# EasyEDA_SmartMeter-Reader.net
KiCad netlist of a schematic drawn in EasyEDA
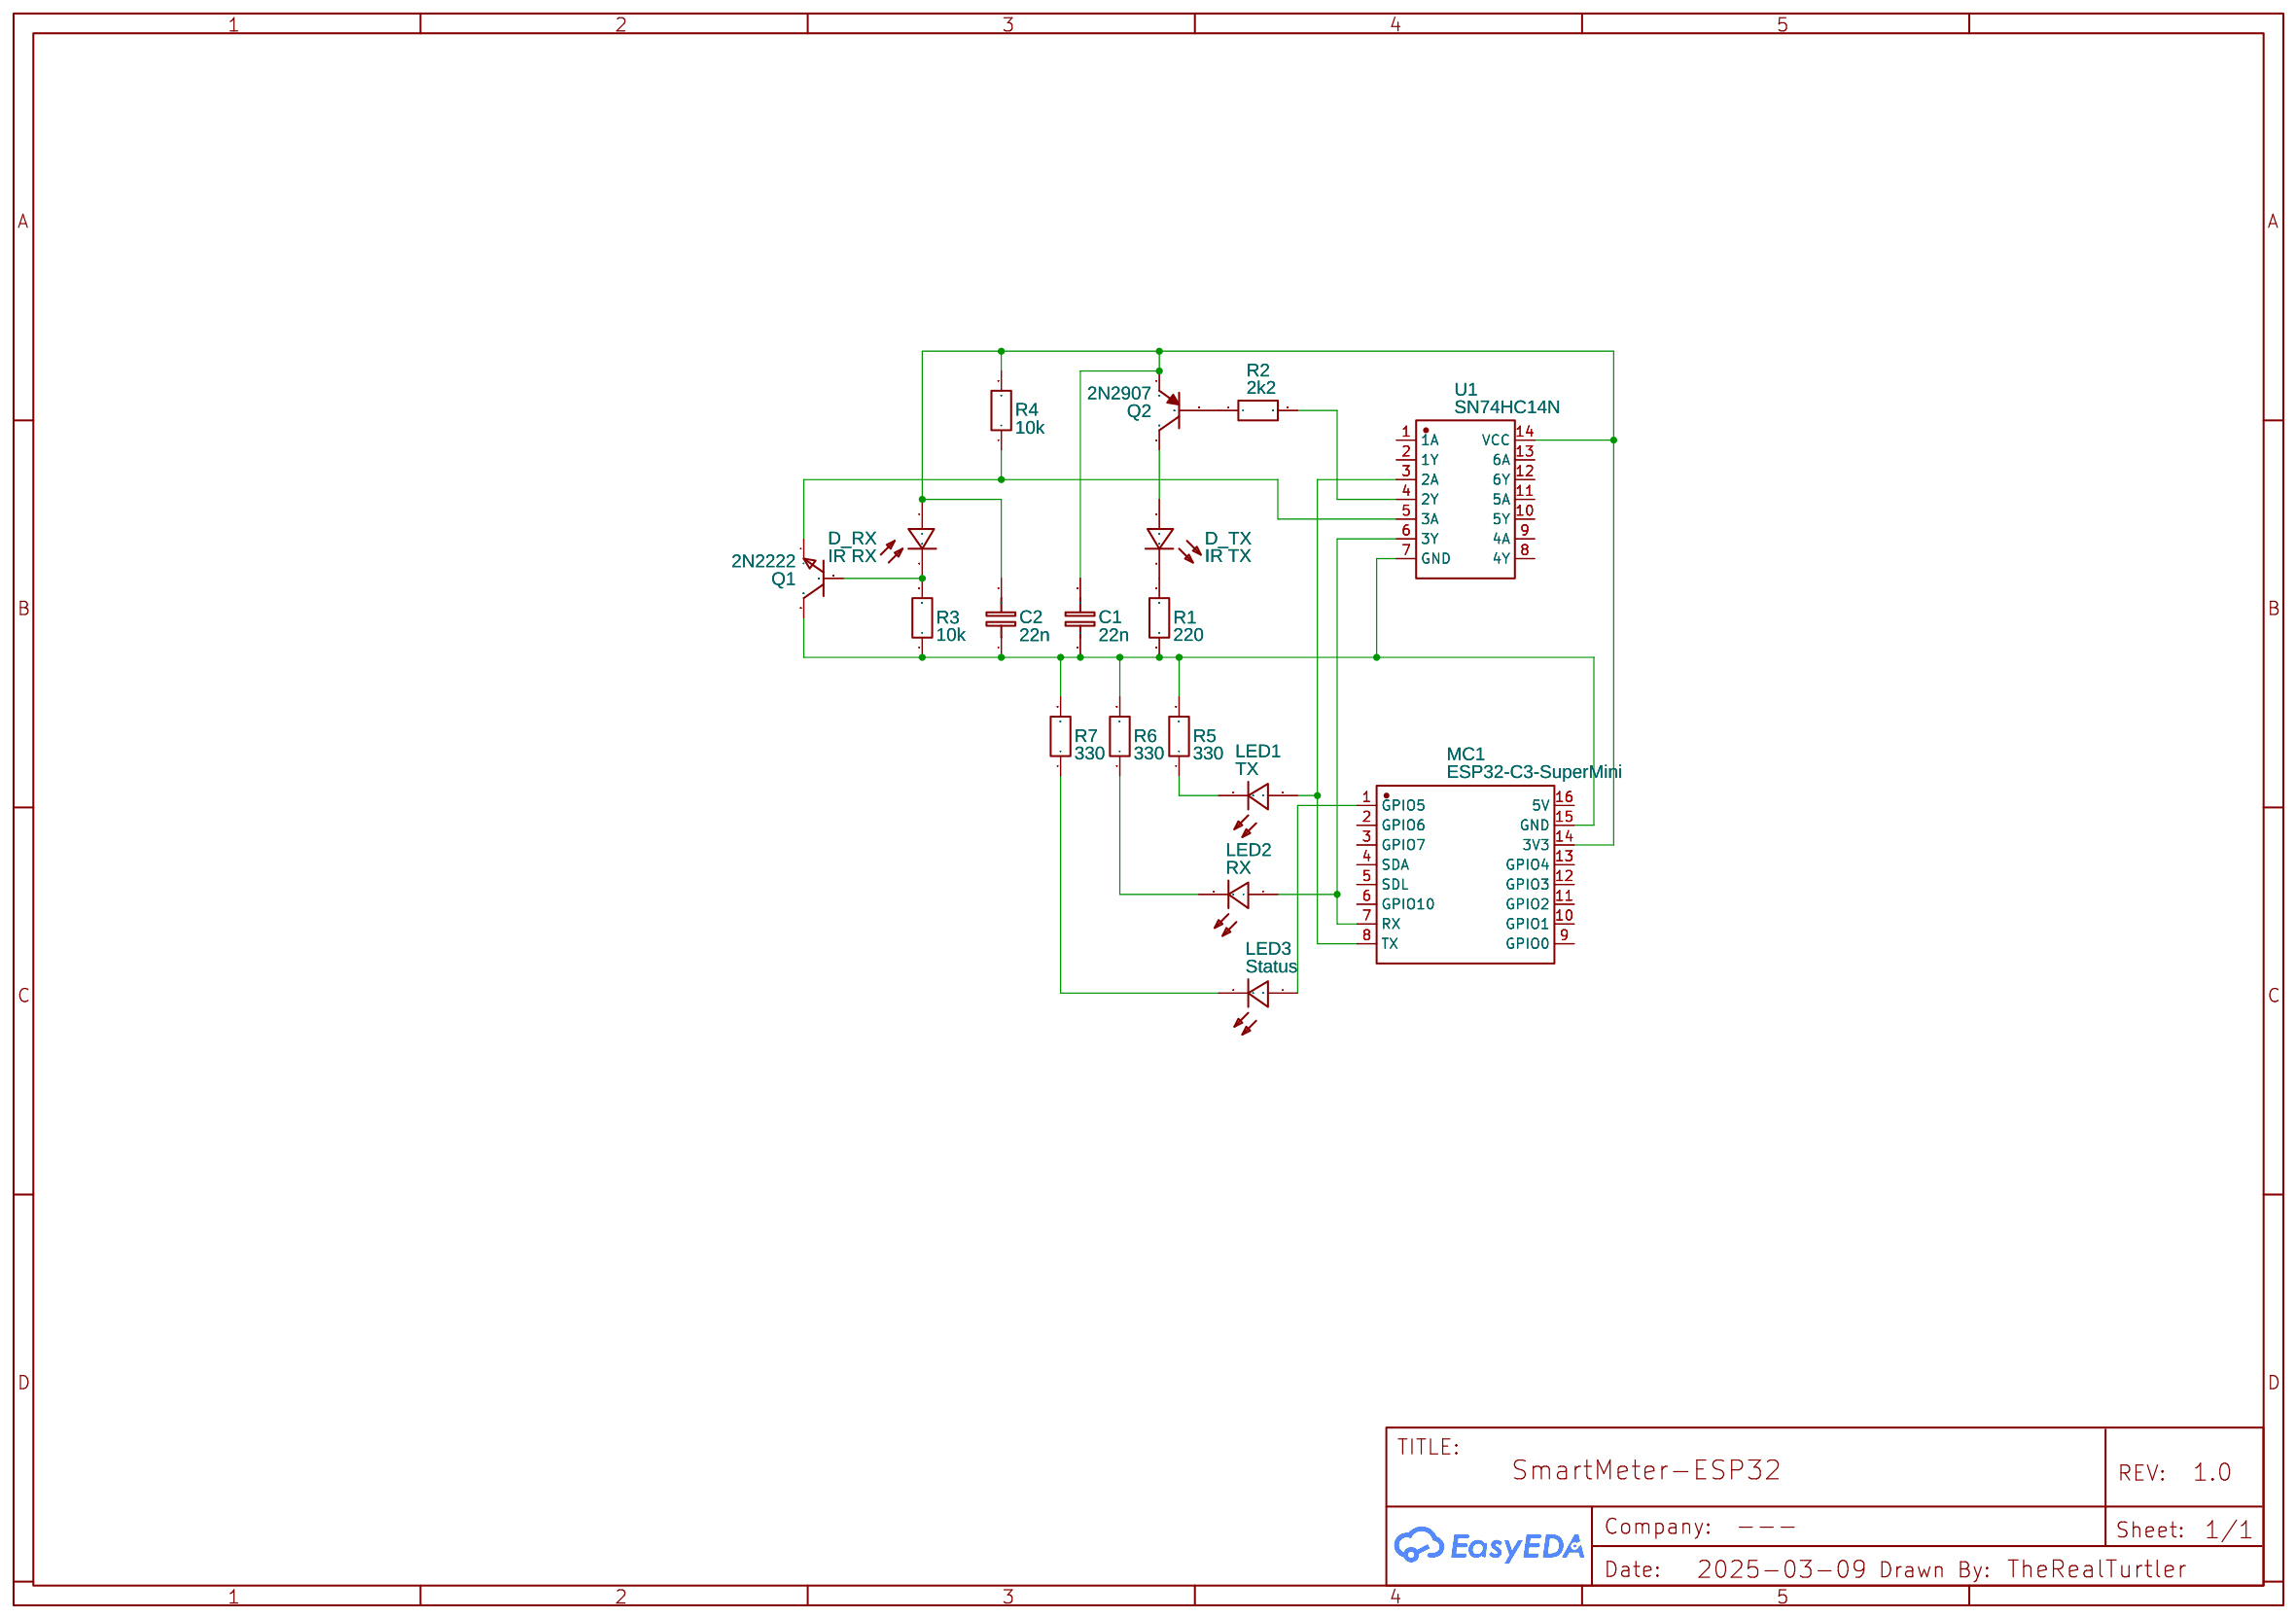
[diagram p0: schematic sheet]

(export (version "E")
  (design (tool "Eeschema 10.0.6"))
  (components
    (comp (ref "C1") (value "22n") (libsource (lib "") (part "C_0603_EU_1")))
    (comp (ref "C2") (value "22n") (libsource (lib "") (part "C_0603_EU")))
    (comp (ref "D_RX") (value "IR RX") (libsource (lib "") (part "Photodiode 3mm")))
    (comp (ref "D_TX")
      (value "IR TX")
      (fields (field (name "Manufacturer Part") "LED-TH-3mm_R"))
      (libsource (lib "") (part "LED-TH-3MM_R"))
    )
    (comp (ref "LED1")
      (value "TX")
      (fields (field (name "Manufacturer Part") "LED-TH-3mm_R"))
      (libsource (lib "") (part "LED-TH-3MM_R_1"))
    )
    (comp (ref "LED2")
      (value "RX")
      (fields (field (name "Manufacturer Part") "LED-TH-3mm_R"))
      (libsource (lib "") (part "LED-TH-3MM_R_1"))
    )
    (comp (ref "LED3")
      (value "Status")
      (fields (field (name "Manufacturer Part") "LED-TH-3mm_R"))
      (libsource (lib "") (part "LED-TH-3MM_R_1"))
    )
    (comp (ref "MC1") (value "ESP32-C3-SuperMini") (libsource (lib "") (part "ESP32-C3-SuperMini")))
    (comp (ref "Q1")
      (value "2N2222")
      (fields (field (name "Manufacturer Part") "2N2222A") (field (name "Manufacturer") "ST(先科)"))
      (libsource (lib "") (part "2N2222"))
    )
    (comp (ref "Q2")
      (value "2N2907")
      (fields (field (name "Manufacturer Part") "2N2907A") (field (name "Manufacturer") "ST(先科)"))
      (libsource (lib "") (part "2N2907"))
    )
    (comp (ref "R1") (value "220") (libsource (lib "") (part "R_0603_EU")))
    (comp (ref "R2") (value "2k2") (libsource (lib "") (part "R_0603_EU_1")))
    (comp (ref "R3") (value "10k") (libsource (lib "") (part "R_0603_EU")))
    (comp (ref "R4") (value "10k") (libsource (lib "") (part "R_0603_EU")))
    (comp (ref "R5") (value "330") (libsource (lib "") (part "R_0603_EU")))
    (comp (ref "R6") (value "330") (libsource (lib "") (part "R_0603_EU")))
    (comp (ref "R7") (value "330") (libsource (lib "") (part "R_0603_EU")))
    (comp (ref "U1")
      (value "SN74HC14N")
      (fields (field (name "Manufacturer") "TI(德州仪器)"))
      (libsource (lib "") (part "SN74HC14N"))
    )
  )
  (nets
    (net (code "1") (name "Net-(D_TX-Pad2)") (class "Default")
      (node (ref "D_TX") (pin "2") (pinfunction "2_2") (pintype "unspecified"))
      (node (ref "R1") (pin "2") (pinfunction "2_2") (pintype "unspecified"))
    )
    (net (code "2") (name "Net-(LED1-Pad2)") (class "Default")
      (node (ref "LED1") (pin "2") (pinfunction "2_2") (pintype "unspecified"))
      (node (ref "R5") (pin "1") (pinfunction "1_1") (pintype "unspecified"))
    )
    (net (code "3") (name "Net-(LED2-Pad2)") (class "Default")
      (node (ref "LED2") (pin "2") (pinfunction "2_2") (pintype "unspecified"))
      (node (ref "R6") (pin "1") (pinfunction "1_1") (pintype "unspecified"))
    )
    (net (code "4") (name "Net-(LED3-Pad2)") (class "Default")
      (node (ref "LED3") (pin "2") (pinfunction "2_2") (pintype "unspecified"))
      (node (ref "R7") (pin "1") (pinfunction "1_1") (pintype "unspecified"))
    )
    (net (code "5") (name "Net-(MC1-3V3)") (class "Default")
      (node (ref "C1") (pin "2") (pinfunction "2_2") (pintype "unspecified"))
      (node (ref "C2") (pin "2") (pinfunction "2_2") (pintype "unspecified"))
      (node (ref "D_RX") (pin "1") (pinfunction "1_1") (pintype "unspecified"))
      (node (ref "MC1") (pin "14") (pinfunction "3V3_14") (pintype "unspecified"))
      (node (ref "Q2") (pin "1") (pinfunction "E_1") (pintype "unspecified"))
      (node (ref "R4") (pin "2") (pinfunction "2_2") (pintype "unspecified"))
      (node (ref "U1") (pin "14") (pinfunction "VCC_14") (pintype "unspecified"))
    )
    (net (code "6") (name "Net-(MC1-GND)") (class "Default")
      (node (ref "C1") (pin "1") (pinfunction "1_1") (pintype "unspecified"))
      (node (ref "C2") (pin "1") (pinfunction "1_1") (pintype "unspecified"))
      (node (ref "MC1") (pin "15") (pinfunction "GND_15") (pintype "unspecified"))
      (node (ref "Q1") (pin "3") (pinfunction "C_3") (pintype "unspecified"))
      (node (ref "R1") (pin "1") (pinfunction "1_1") (pintype "unspecified"))
      (node (ref "R3") (pin "1") (pinfunction "1_1") (pintype "unspecified"))
      (node (ref "R5") (pin "2") (pinfunction "2_2") (pintype "unspecified"))
      (node (ref "R6") (pin "2") (pinfunction "2_2") (pintype "unspecified"))
      (node (ref "R7") (pin "2") (pinfunction "2_2") (pintype "unspecified"))
      (node (ref "U1") (pin "7") (pinfunction "GND_7") (pintype "unspecified"))
    )
    (net (code "7") (name "Net-(MC1-GPIO5)") (class "Default")
      (node (ref "LED3") (pin "1") (pinfunction "1_1") (pintype "unspecified"))
      (node (ref "MC1") (pin "1") (pinfunction "GPIO5_1") (pintype "unspecified"))
    )
    (net (code "8") (name "Net-(MC1-RX)") (class "Default")
      (node (ref "LED2") (pin "1") (pinfunction "1_1") (pintype "unspecified"))
      (node (ref "MC1") (pin "7") (pinfunction "RX_7") (pintype "unspecified"))
      (node (ref "U1") (pin "6") (pinfunction "3Y_6") (pintype "unspecified"))
    )
    (net (code "9") (name "Net-(MC1-TX)") (class "Default")
      (node (ref "LED1") (pin "1") (pinfunction "1_1") (pintype "unspecified"))
      (node (ref "MC1") (pin "8") (pinfunction "TX_8") (pintype "unspecified"))
      (node (ref "U1") (pin "3") (pinfunction "2A_3") (pintype "unspecified"))
    )
    (net (code "10") (name "Net-(Q1-B)") (class "Default")
      (node (ref "D_RX") (pin "2") (pinfunction "2_2") (pintype "unspecified"))
      (node (ref "Q1") (pin "2") (pinfunction "B_2") (pintype "unspecified"))
      (node (ref "R3") (pin "2") (pinfunction "2_2") (pintype "unspecified"))
    )
    (net (code "11") (name "Net-(Q1-E)") (class "Default")
      (node (ref "Q1") (pin "1") (pinfunction "E_1") (pintype "unspecified"))
      (node (ref "R4") (pin "1") (pinfunction "1_1") (pintype "unspecified"))
      (node (ref "U1") (pin "5") (pinfunction "3A_5") (pintype "unspecified"))
    )
    (net (code "12") (name "Net-(Q2-B)") (class "Default")
      (node (ref "Q2") (pin "2") (pinfunction "B_2") (pintype "unspecified"))
      (node (ref "R2") (pin "1") (pinfunction "1_1") (pintype "unspecified"))
    )
    (net (code "13") (name "Net-(Q2-C)") (class "Default")
      (node (ref "D_TX") (pin "1") (pinfunction "1_1") (pintype "unspecified"))
      (node (ref "Q2") (pin "3") (pinfunction "C_3") (pintype "unspecified"))
    )
    (net (code "14") (name "Net-(U1-2Y)") (class "Default")
      (node (ref "R2") (pin "2") (pinfunction "2_2") (pintype "unspecified"))
      (node (ref "U1") (pin "4") (pinfunction "2Y_4") (pintype "unspecified"))
    )
    (net (code "15") (name "unconnected-(MC1-5V-Pad16)") (class "Default")
      (node (ref "MC1") (pin "16") (pinfunction "5V_16") (pintype "unspecified"))
    )
    (net (code "16") (name "unconnected-(MC1-GPIO0-Pad9)") (class "Default")
      (node (ref "MC1") (pin "9") (pinfunction "GPIO0_9") (pintype "unspecified"))
    )
    (net (code "17") (name "unconnected-(MC1-GPIO1-Pad10)") (class "Default")
      (node (ref "MC1") (pin "10") (pinfunction "GPIO1_10") (pintype "unspecified"))
    )
    (net (code "18") (name "unconnected-(MC1-GPIO2-Pad11)") (class "Default")
      (node (ref "MC1") (pin "11") (pinfunction "GPIO2_11") (pintype "unspecified"))
    )
    (net (code "19") (name "unconnected-(MC1-GPIO3-Pad12)") (class "Default")
      (node (ref "MC1") (pin "12") (pinfunction "GPIO3_12") (pintype "unspecified"))
    )
    (net (code "20") (name "unconnected-(MC1-GPIO4-Pad13)") (class "Default")
      (node (ref "MC1") (pin "13") (pinfunction "GPIO4_13") (pintype "unspecified"))
    )
    (net (code "21") (name "unconnected-(MC1-GPIO6-Pad2)") (class "Default")
      (node (ref "MC1") (pin "2") (pinfunction "GPIO6_2") (pintype "unspecified"))
    )
    (net (code "22") (name "unconnected-(MC1-GPIO7-Pad3)") (class "Default")
      (node (ref "MC1") (pin "3") (pinfunction "GPIO7_3") (pintype "unspecified"))
    )
    (net (code "23") (name "unconnected-(MC1-GPIO10-Pad6)") (class "Default")
      (node (ref "MC1") (pin "6") (pinfunction "GPIO10_6") (pintype "unspecified"))
    )
    (net (code "24") (name "unconnected-(MC1-SDA-Pad4)") (class "Default")
      (node (ref "MC1") (pin "4") (pinfunction "SDA_4") (pintype "unspecified"))
    )
    (net (code "25") (name "unconnected-(MC1-SDL-Pad5)") (class "Default")
      (node (ref "MC1") (pin "5") (pinfunction "SDL_5") (pintype "unspecified"))
    )
    (net (code "26") (name "unconnected-(U1-1A-Pad1)") (class "Default")
      (node (ref "U1") (pin "1") (pinfunction "1A_1") (pintype "unspecified"))
    )
    (net (code "27") (name "unconnected-(U1-1Y-Pad2)") (class "Default")
      (node (ref "U1") (pin "2") (pinfunction "1Y_2") (pintype "unspecified"))
    )
    (net (code "28") (name "unconnected-(U1-4A-Pad9)") (class "Default")
      (node (ref "U1") (pin "9") (pinfunction "4A_9") (pintype "unspecified"))
    )
    (net (code "29") (name "unconnected-(U1-4Y-Pad8)") (class "Default")
      (node (ref "U1") (pin "8") (pinfunction "4Y_8") (pintype "unspecified"))
    )
    (net (code "30") (name "unconnected-(U1-5A-Pad11)") (class "Default")
      (node (ref "U1") (pin "11") (pinfunction "5A_11") (pintype "unspecified"))
    )
    (net (code "31") (name "unconnected-(U1-5Y-Pad10)") (class "Default")
      (node (ref "U1") (pin "10") (pinfunction "5Y_10") (pintype "unspecified"))
    )
    (net (code "32") (name "unconnected-(U1-6A-Pad13)") (class "Default")
      (node (ref "U1") (pin "13") (pinfunction "6A_13") (pintype "unspecified"))
    )
    (net (code "33") (name "unconnected-(U1-6Y-Pad12)") (class "Default")
      (node (ref "U1") (pin "12") (pinfunction "6Y_12") (pintype "unspecified"))
    )
  )
)
